# 2_3_4.net
KiCad netlist of a schematic drawn in EasyEDA
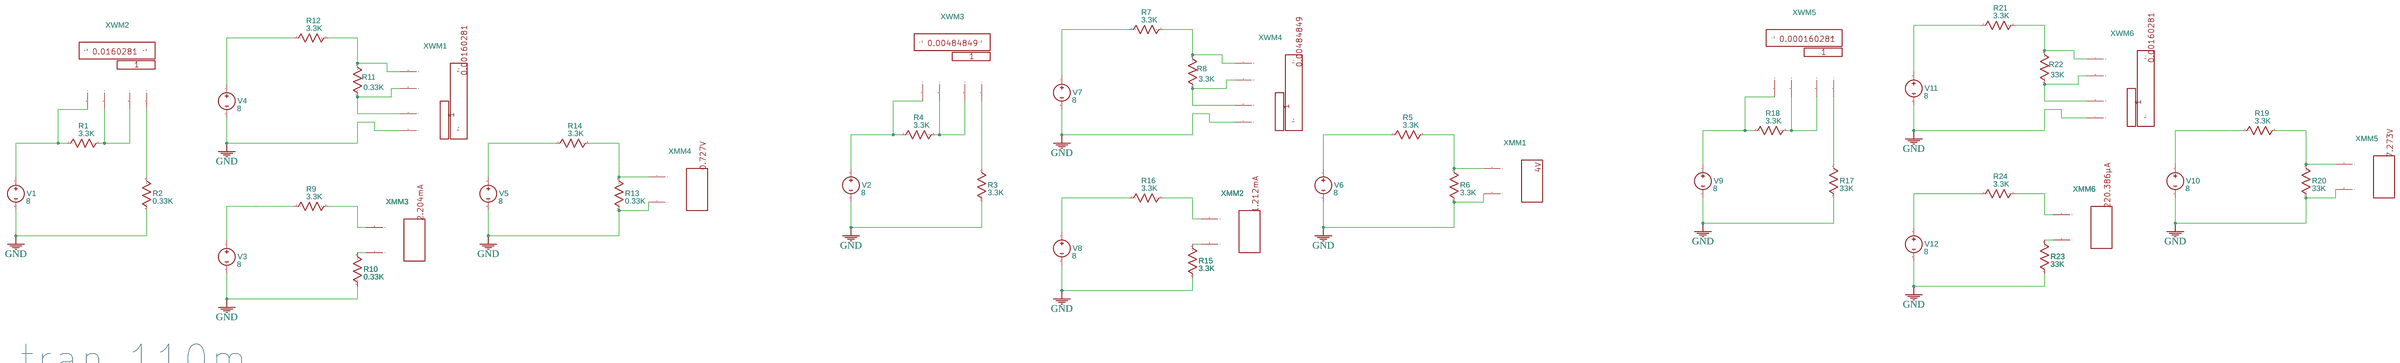
[diagram p0: schematic sheet]

(export (version "E")
  (design (tool "Eeschema 10.0.6"))
  (components
    (comp (ref "R1") (value "3.3K") (libsource (lib "") (part "Resistor_US")))
    (comp (ref "R2") (value "0.33K") (libsource (lib "") (part "Resistor_US_1")))
    (comp (ref "R3") (value "3.3K") (libsource (lib "") (part "Resistor_US_1")))
    (comp (ref "R4") (value "3.3K") (libsource (lib "") (part "Resistor_US")))
    (comp (ref "R5") (value "3.3K") (libsource (lib "") (part "Resistor_US")))
    (comp (ref "R6") (value "3.3K") (libsource (lib "") (part "Resistor_US_1")))
    (comp (ref "R7") (value "3.3K") (libsource (lib "") (part "Resistor_US")))
    (comp (ref "R8") (value "3.3K") (libsource (lib "") (part "Resistor_US_1")))
    (comp (ref "R9") (value "3.3K") (libsource (lib "") (part "Resistor_US")))
    (comp (ref "R10") (value "0.33K") (libsource (lib "") (part "Resistor_US_1")))
    (comp (ref "R11") (value "0.33K") (libsource (lib "") (part "Resistor_US_1")))
    (comp (ref "R12") (value "3.3K") (libsource (lib "") (part "Resistor_US")))
    (comp (ref "R13") (value "0.33K") (libsource (lib "") (part "Resistor_US_1")))
    (comp (ref "R14") (value "3.3K") (libsource (lib "") (part "Resistor_US")))
    (comp (ref "R15") (value "3.3K") (libsource (lib "") (part "Resistor_US_1")))
    (comp (ref "R16") (value "3.3K") (libsource (lib "") (part "Resistor_US")))
    (comp (ref "R17") (value "33K") (libsource (lib "") (part "Resistor_US_1")))
    (comp (ref "R18") (value "3.3K") (libsource (lib "") (part "Resistor_US")))
    (comp (ref "R19") (value "3.3K") (libsource (lib "") (part "Resistor_US")))
    (comp (ref "R20") (value "33K") (libsource (lib "") (part "Resistor_US_1")))
    (comp (ref "R21") (value "3.3K") (libsource (lib "") (part "Resistor_US")))
    (comp (ref "R22") (value "33K") (libsource (lib "") (part "Resistor_US_1")))
    (comp (ref "R23") (value "33K") (libsource (lib "") (part "Resistor_US_1")))
    (comp (ref "R24") (value "3.3K") (libsource (lib "") (part "Resistor_US")))
    (comp (ref "V1") (value "8") (libsource (lib "") (part "VDC")))
    (comp (ref "V2") (value "8") (libsource (lib "") (part "VDC")))
    (comp (ref "V3") (value "8") (libsource (lib "") (part "VDC")))
    (comp (ref "V4") (value "8") (libsource (lib "") (part "VDC")))
    (comp (ref "V5") (value "8") (libsource (lib "") (part "VDC")))
    (comp (ref "V6") (value "8") (libsource (lib "") (part "VDC")))
    (comp (ref "V7") (value "8") (libsource (lib "") (part "VDC")))
    (comp (ref "V8") (value "8") (libsource (lib "") (part "VDC")))
    (comp (ref "V9") (value "8") (libsource (lib "") (part "VDC")))
    (comp (ref "V10") (value "8") (libsource (lib "") (part "VDC")))
    (comp (ref "V11") (value "8") (libsource (lib "") (part "VDC")))
    (comp (ref "V12") (value "8") (libsource (lib "") (part "VDC")))
    (comp (ref "XMM1") (value "Multimeter") (libsource (lib "") (part "MULTIMETER_2")))
    (comp (ref "XMM2") (value "Multimeter") (libsource (lib "") (part "MULTIMETER_1")))
    (comp (ref "XMM3") (value "Multimeter") (libsource (lib "") (part "MULTIMETER_3")))
    (comp (ref "XMM4") (value "Multimeter") (libsource (lib "") (part "MULTIMETER_4")))
    (comp (ref "XMM5") (value "Multimeter") (libsource (lib "") (part "MULTIMETER_5")))
    (comp (ref "XMM6") (value "Multimeter") (libsource (lib "") (part "MULTIMETER")))
    (comp (ref "XWM1") (value "Wattmeter") (libsource (lib "") (part "WATTMETER")))
    (comp (ref "XWM2") (value "Wattmeter") (libsource (lib "") (part "WATTMETER_1")))
    (comp (ref "XWM3") (value "Wattmeter") (libsource (lib "") (part "WATTMETER_2")))
    (comp (ref "XWM4") (value "Wattmeter") (libsource (lib "") (part "WATTMETER_4")))
    (comp (ref "XWM5") (value "Wattmeter") (libsource (lib "") (part "WATTMETER_3")))
    (comp (ref "XWM6") (value "Wattmeter") (libsource (lib "") (part "WATTMETER")))
  )
  (nets
    (net (code "1") (name "GND") (class "Default")
      (node (ref "R10") (pin "1") (pinfunction "1_1") (pintype "unspecified"))
      (node (ref "R13") (pin "1") (pinfunction "1_1") (pintype "unspecified"))
      (node (ref "R15") (pin "1") (pinfunction "1_1") (pintype "unspecified"))
      (node (ref "R17") (pin "1") (pinfunction "1_1") (pintype "unspecified"))
      (node (ref "R2") (pin "1") (pinfunction "1_1") (pintype "unspecified"))
      (node (ref "R20") (pin "1") (pinfunction "1_1") (pintype "unspecified"))
      (node (ref "R23") (pin "1") (pinfunction "1_1") (pintype "unspecified"))
      (node (ref "R3") (pin "1") (pinfunction "1_1") (pintype "unspecified"))
      (node (ref "R6") (pin "1") (pinfunction "1_1") (pintype "unspecified"))
      (node (ref "V1") (pin "2") (pinfunction "2_2") (pintype "unspecified"))
      (node (ref "V10") (pin "2") (pinfunction "2_2") (pintype "unspecified"))
      (node (ref "V11") (pin "2") (pinfunction "2_2") (pintype "unspecified"))
      (node (ref "V12") (pin "2") (pinfunction "2_2") (pintype "unspecified"))
      (node (ref "V2") (pin "2") (pinfunction "2_2") (pintype "unspecified"))
      (node (ref "V3") (pin "2") (pinfunction "2_2") (pintype "unspecified"))
      (node (ref "V4") (pin "2") (pinfunction "2_2") (pintype "unspecified"))
      (node (ref "V5") (pin "2") (pinfunction "2_2") (pintype "unspecified"))
      (node (ref "V6") (pin "2") (pinfunction "2_2") (pintype "unspecified"))
      (node (ref "V7") (pin "2") (pinfunction "2_2") (pintype "unspecified"))
      (node (ref "V8") (pin "2") (pinfunction "2_2") (pintype "unspecified"))
      (node (ref "V9") (pin "2") (pinfunction "2_2") (pintype "unspecified"))
      (node (ref "XMM1") (pin "2") (pinfunction "I_2") (pintype "unspecified"))
      (node (ref "XMM4") (pin "2") (pinfunction "I_2") (pintype "unspecified"))
      (node (ref "XMM5") (pin "2") (pinfunction "I_2") (pintype "unspecified"))
      (node (ref "XWM1") (pin "4") (pinfunction "I-_4") (pintype "unspecified"))
      (node (ref "XWM4") (pin "4") (pinfunction "I-_4") (pintype "unspecified"))
      (node (ref "XWM6") (pin "4") (pinfunction "I-_4") (pintype "unspecified"))
    )
    (net (code "2") (name "Net-(R5-Pad1)") (class "Default")
      (node (ref "R5") (pin "1") (pinfunction "1_1") (pintype "unspecified"))
      (node (ref "V6") (pin "1") (pinfunction "1_1") (pintype "unspecified"))
    )
    (net (code "3") (name "Net-(R7-Pad1)") (class "Default")
      (node (ref "R7") (pin "1") (pinfunction "1_1") (pintype "unspecified"))
      (node (ref "V7") (pin "1") (pinfunction "1_1") (pintype "unspecified"))
    )
    (net (code "4") (name "Net-(R9-Pad1)") (class "Default")
      (node (ref "R9") (pin "1") (pinfunction "1_1") (pintype "unspecified"))
      (node (ref "V3") (pin "1") (pinfunction "1_1") (pintype "unspecified"))
    )
    (net (code "5") (name "Net-(R12-Pad1)") (class "Default")
      (node (ref "R12") (pin "1") (pinfunction "1_1") (pintype "unspecified"))
      (node (ref "V4") (pin "1") (pinfunction "1_1") (pintype "unspecified"))
    )
    (net (code "6") (name "Net-(R14-Pad1)") (class "Default")
      (node (ref "R14") (pin "1") (pinfunction "1_1") (pintype "unspecified"))
      (node (ref "V5") (pin "1") (pinfunction "1_1") (pintype "unspecified"))
    )
    (net (code "7") (name "Net-(R16-Pad1)") (class "Default")
      (node (ref "R16") (pin "1") (pinfunction "1_1") (pintype "unspecified"))
      (node (ref "V8") (pin "1") (pinfunction "1_1") (pintype "unspecified"))
    )
    (net (code "8") (name "Net-(R19-Pad1)") (class "Default")
      (node (ref "R19") (pin "1") (pinfunction "1_1") (pintype "unspecified"))
      (node (ref "V10") (pin "1") (pinfunction "1_1") (pintype "unspecified"))
    )
    (net (code "9") (name "Net-(R21-Pad1)") (class "Default")
      (node (ref "R21") (pin "1") (pinfunction "1_1") (pintype "unspecified"))
      (node (ref "V11") (pin "1") (pinfunction "1_1") (pintype "unspecified"))
    )
    (net (code "10") (name "Net-(R24-Pad1)") (class "Default")
      (node (ref "R24") (pin "1") (pinfunction "1_1") (pintype "unspecified"))
      (node (ref "V12") (pin "1") (pinfunction "1_1") (pintype "unspecified"))
    )
    (net (code "11") (name "Net-(XMM1-+)") (class "Default")
      (node (ref "R5") (pin "2") (pinfunction "2_2") (pintype "unspecified"))
      (node (ref "R6") (pin "2") (pinfunction "2_2") (pintype "unspecified"))
      (node (ref "XMM1") (pin "1") (pinfunction "+_1") (pintype "unspecified"))
    )
    (net (code "12") (name "Net-(XMM2-+)") (class "Default")
      (node (ref "R16") (pin "2") (pinfunction "2_2") (pintype "unspecified"))
      (node (ref "XMM2") (pin "1") (pinfunction "+_1") (pintype "unspecified"))
    )
    (net (code "13") (name "Net-(XMM2-I)") (class "Default")
      (node (ref "R15") (pin "2") (pinfunction "2_2") (pintype "unspecified"))
      (node (ref "XMM2") (pin "2") (pinfunction "I_2") (pintype "unspecified"))
    )
    (net (code "14") (name "Net-(XMM3-+)") (class "Default")
      (node (ref "R9") (pin "2") (pinfunction "2_2") (pintype "unspecified"))
      (node (ref "XMM3") (pin "1") (pinfunction "+_1") (pintype "unspecified"))
    )
    (net (code "15") (name "Net-(XMM3-I)") (class "Default")
      (node (ref "R10") (pin "2") (pinfunction "2_2") (pintype "unspecified"))
      (node (ref "XMM3") (pin "2") (pinfunction "I_2") (pintype "unspecified"))
    )
    (net (code "16") (name "Net-(XMM4-+)") (class "Default")
      (node (ref "R13") (pin "2") (pinfunction "2_2") (pintype "unspecified"))
      (node (ref "R14") (pin "2") (pinfunction "2_2") (pintype "unspecified"))
      (node (ref "XMM4") (pin "1") (pinfunction "+_1") (pintype "unspecified"))
    )
    (net (code "17") (name "Net-(XMM5-+)") (class "Default")
      (node (ref "R19") (pin "2") (pinfunction "2_2") (pintype "unspecified"))
      (node (ref "R20") (pin "2") (pinfunction "2_2") (pintype "unspecified"))
      (node (ref "XMM5") (pin "1") (pinfunction "+_1") (pintype "unspecified"))
    )
    (net (code "18") (name "Net-(XMM6-+)") (class "Default")
      (node (ref "R24") (pin "2") (pinfunction "2_2") (pintype "unspecified"))
      (node (ref "XMM6") (pin "1") (pinfunction "+_1") (pintype "unspecified"))
    )
    (net (code "19") (name "Net-(XMM6-I)") (class "Default")
      (node (ref "R23") (pin "2") (pinfunction "2_2") (pintype "unspecified"))
      (node (ref "XMM6") (pin "2") (pinfunction "I_2") (pintype "unspecified"))
    )
    (net (code "20") (name "Net-(XWM1-I+)") (class "Default")
      (node (ref "R11") (pin "1") (pinfunction "1_1") (pintype "unspecified"))
      (node (ref "XWM1") (pin "2") (pinfunction "V-_2") (pintype "unspecified"))
      (node (ref "XWM1") (pin "3") (pinfunction "I+_3") (pintype "unspecified"))
    )
    (net (code "21") (name "Net-(XWM1-V+)") (class "Default")
      (node (ref "R11") (pin "2") (pinfunction "2_2") (pintype "unspecified"))
      (node (ref "R12") (pin "2") (pinfunction "2_2") (pintype "unspecified"))
      (node (ref "XWM1") (pin "1") (pinfunction "V+_1") (pintype "unspecified"))
    )
    (net (code "22") (name "Net-(XWM2-I+)") (class "Default")
      (node (ref "R1") (pin "2") (pinfunction "2_2") (pintype "unspecified"))
      (node (ref "XWM2") (pin "2") (pinfunction "V-_2") (pintype "unspecified"))
      (node (ref "XWM2") (pin "3") (pinfunction "I+_3") (pintype "unspecified"))
    )
    (net (code "23") (name "Net-(XWM2-I-)") (class "Default")
      (node (ref "R2") (pin "2") (pinfunction "2_2") (pintype "unspecified"))
      (node (ref "XWM2") (pin "4") (pinfunction "I-_4") (pintype "unspecified"))
    )
    (net (code "24") (name "Net-(XWM2-V+)") (class "Default")
      (node (ref "R1") (pin "1") (pinfunction "1_1") (pintype "unspecified"))
      (node (ref "V1") (pin "1") (pinfunction "1_1") (pintype "unspecified"))
      (node (ref "XWM2") (pin "1") (pinfunction "V+_1") (pintype "unspecified"))
    )
    (net (code "25") (name "Net-(XWM3-I+)") (class "Default")
      (node (ref "R4") (pin "2") (pinfunction "2_2") (pintype "unspecified"))
      (node (ref "XWM3") (pin "2") (pinfunction "V-_2") (pintype "unspecified"))
      (node (ref "XWM3") (pin "3") (pinfunction "I+_3") (pintype "unspecified"))
    )
    (net (code "26") (name "Net-(XWM3-I-)") (class "Default")
      (node (ref "R3") (pin "2") (pinfunction "2_2") (pintype "unspecified"))
      (node (ref "XWM3") (pin "4") (pinfunction "I-_4") (pintype "unspecified"))
    )
    (net (code "27") (name "Net-(XWM3-V+)") (class "Default")
      (node (ref "R4") (pin "1") (pinfunction "1_1") (pintype "unspecified"))
      (node (ref "V2") (pin "1") (pinfunction "1_1") (pintype "unspecified"))
      (node (ref "XWM3") (pin "1") (pinfunction "V+_1") (pintype "unspecified"))
    )
    (net (code "28") (name "Net-(XWM4-I+)") (class "Default")
      (node (ref "R8") (pin "1") (pinfunction "1_1") (pintype "unspecified"))
      (node (ref "XWM4") (pin "2") (pinfunction "V-_2") (pintype "unspecified"))
      (node (ref "XWM4") (pin "3") (pinfunction "I+_3") (pintype "unspecified"))
    )
    (net (code "29") (name "Net-(XWM4-V+)") (class "Default")
      (node (ref "R7") (pin "2") (pinfunction "2_2") (pintype "unspecified"))
      (node (ref "R8") (pin "2") (pinfunction "2_2") (pintype "unspecified"))
      (node (ref "XWM4") (pin "1") (pinfunction "V+_1") (pintype "unspecified"))
    )
    (net (code "30") (name "Net-(XWM5-I+)") (class "Default")
      (node (ref "R18") (pin "2") (pinfunction "2_2") (pintype "unspecified"))
      (node (ref "XWM5") (pin "2") (pinfunction "V-_2") (pintype "unspecified"))
      (node (ref "XWM5") (pin "3") (pinfunction "I+_3") (pintype "unspecified"))
    )
    (net (code "31") (name "Net-(XWM5-I-)") (class "Default")
      (node (ref "R17") (pin "2") (pinfunction "2_2") (pintype "unspecified"))
      (node (ref "XWM5") (pin "4") (pinfunction "I-_4") (pintype "unspecified"))
    )
    (net (code "32") (name "Net-(XWM5-V+)") (class "Default")
      (node (ref "R18") (pin "1") (pinfunction "1_1") (pintype "unspecified"))
      (node (ref "V9") (pin "1") (pinfunction "1_1") (pintype "unspecified"))
      (node (ref "XWM5") (pin "1") (pinfunction "V+_1") (pintype "unspecified"))
    )
    (net (code "33") (name "Net-(XWM6-I+)") (class "Default")
      (node (ref "R22") (pin "1") (pinfunction "1_1") (pintype "unspecified"))
      (node (ref "XWM6") (pin "2") (pinfunction "V-_2") (pintype "unspecified"))
      (node (ref "XWM6") (pin "3") (pinfunction "I+_3") (pintype "unspecified"))
    )
    (net (code "34") (name "Net-(XWM6-V+)") (class "Default")
      (node (ref "R21") (pin "2") (pinfunction "2_2") (pintype "unspecified"))
      (node (ref "R22") (pin "2") (pinfunction "2_2") (pintype "unspecified"))
      (node (ref "XWM6") (pin "1") (pinfunction "V+_1") (pintype "unspecified"))
    )
    (net (code "35") (name "unconnected-(XWM1-PadP)") (class "Default")
      (node (ref "XWM1") (pin "P") (pinfunction "P_P") (pintype "unspecified"))
    )
    (net (code "36") (name "unconnected-(XWM1-PadPF)") (class "Default")
      (node (ref "XWM1") (pin "PF") (pinfunction "PF_PF") (pintype "unspecified"))
    )
    (net (code "37") (name "unconnected-(XWM2-PadP)") (class "Default")
      (node (ref "XWM2") (pin "P") (pinfunction "P_P") (pintype "unspecified"))
    )
    (net (code "38") (name "unconnected-(XWM2-PadPF)") (class "Default")
      (node (ref "XWM2") (pin "PF") (pinfunction "PF_PF") (pintype "unspecified"))
    )
    (net (code "39") (name "unconnected-(XWM3-PadP)") (class "Default")
      (node (ref "XWM3") (pin "P") (pinfunction "P_P") (pintype "unspecified"))
    )
    (net (code "40") (name "unconnected-(XWM3-PadPF)") (class "Default")
      (node (ref "XWM3") (pin "PF") (pinfunction "PF_PF") (pintype "unspecified"))
    )
    (net (code "41") (name "unconnected-(XWM4-PadP)") (class "Default")
      (node (ref "XWM4") (pin "P") (pinfunction "P_P") (pintype "unspecified"))
    )
    (net (code "42") (name "unconnected-(XWM4-PadPF)") (class "Default")
      (node (ref "XWM4") (pin "PF") (pinfunction "PF_PF") (pintype "unspecified"))
    )
    (net (code "43") (name "unconnected-(XWM5-PadP)") (class "Default")
      (node (ref "XWM5") (pin "P") (pinfunction "P_P") (pintype "unspecified"))
    )
    (net (code "44") (name "unconnected-(XWM5-PadPF)") (class "Default")
      (node (ref "XWM5") (pin "PF") (pinfunction "PF_PF") (pintype "unspecified"))
    )
    (net (code "45") (name "unconnected-(XWM6-PadP)") (class "Default")
      (node (ref "XWM6") (pin "P") (pinfunction "P_P") (pintype "unspecified"))
    )
    (net (code "46") (name "unconnected-(XWM6-PadPF)") (class "Default")
      (node (ref "XWM6") (pin "PF") (pinfunction "PF_PF") (pintype "unspecified"))
    )
  )
)
